# Parallel_CS_V3.net
KiCad netlist of a schematic drawn in EAGLE
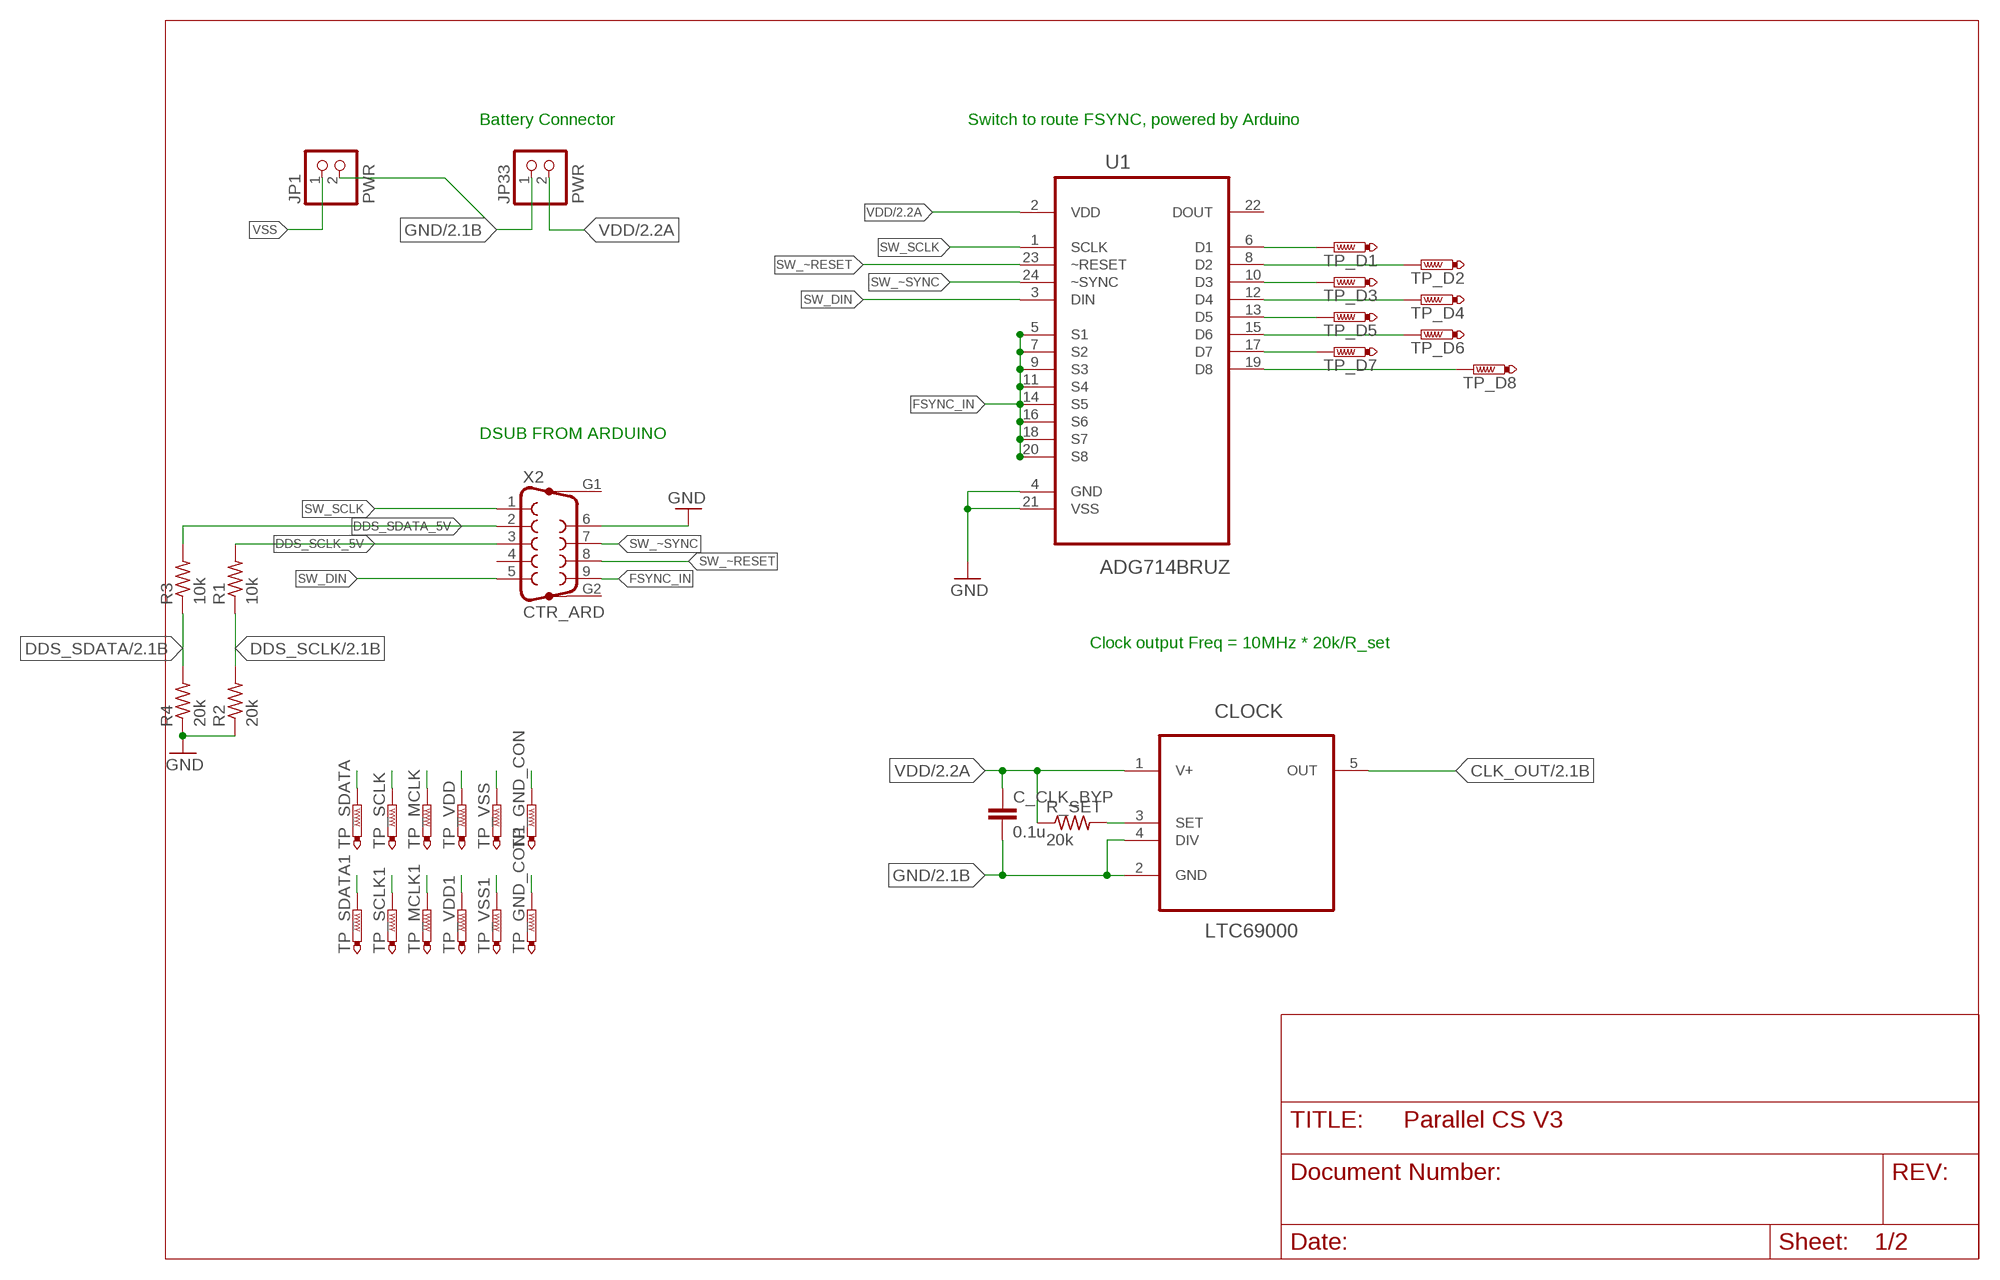
[diagram p0: schematic, sheet 1]
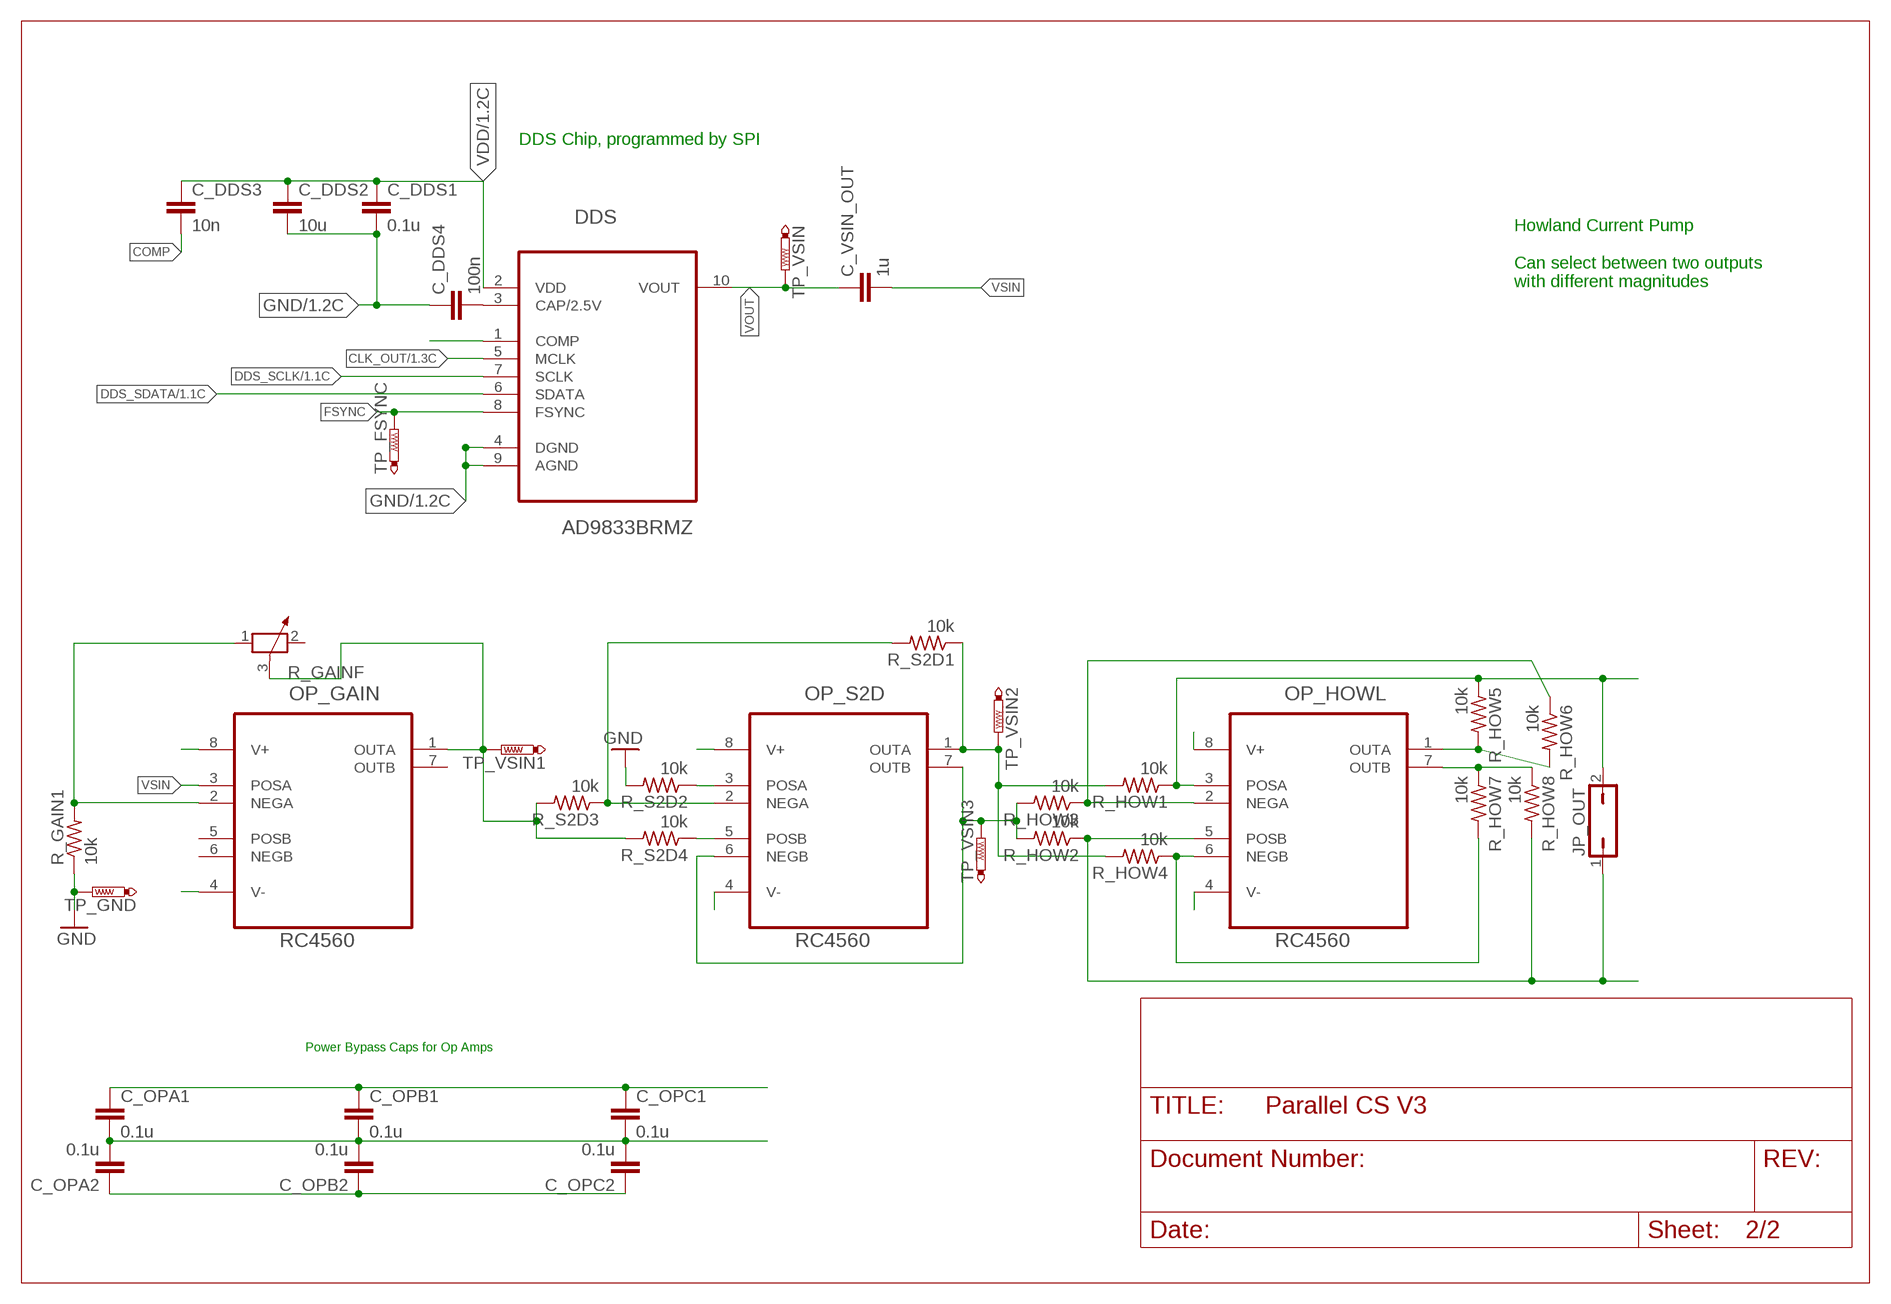
[diagram p1: schematic, sheet 2]

(export (version "E")
  (design (tool "Eeschema 10.0.6"))
  (components
    (comp (ref "C_DDS1")
      (value "0.1u")
      (footprint "eagle-import:C0805")
      (libsource (lib "eagle-import") (part "C-EUC0805"))
    )
    (comp (ref "C_DDS2")
      (value "10u")
      (footprint "eagle-import:C0805")
      (libsource (lib "eagle-import") (part "C-EUC0805"))
    )
    (comp (ref "C_DDS3")
      (value "10n")
      (footprint "eagle-import:C0805")
      (libsource (lib "eagle-import") (part "C-EUC0805"))
    )
    (comp (ref "C_DDS4")
      (value "100n")
      (footprint "eagle-import:C0805")
      (libsource (lib "eagle-import") (part "C-EUC0805"))
    )
    (comp (ref "C_OPA1")
      (value "0.1u")
      (footprint "eagle-import:C0805")
      (libsource (lib "eagle-import") (part "C-EUC0805"))
    )
    (comp (ref "C_OPA2")
      (value "0.1u")
      (footprint "eagle-import:C0805")
      (libsource (lib "eagle-import") (part "C-EUC0805"))
    )
    (comp (ref "C_OPB1")
      (value "0.1u")
      (footprint "eagle-import:C0805")
      (libsource (lib "eagle-import") (part "C-EUC0805"))
    )
    (comp (ref "C_OPB2")
      (value "0.1u")
      (footprint "eagle-import:C0805")
      (libsource (lib "eagle-import") (part "C-EUC0805"))
    )
    (comp (ref "C_OPC1")
      (value "0.1u")
      (footprint "eagle-import:C0805")
      (libsource (lib "eagle-import") (part "C-EUC0805"))
    )
    (comp (ref "C_OPC2")
      (value "0.1u")
      (footprint "eagle-import:C0805")
      (libsource (lib "eagle-import") (part "C-EUC0805"))
    )
    (comp (ref "C_VSIN_OUT")
      (value "1u")
      (footprint "eagle-import:C0805")
      (libsource (lib "eagle-import") (part "C-EUC0805"))
    )
    (comp (ref "DDS")
      (value "AD9833BRMZ")
      (footprint "eagle-import:SOP50P490X110-10N")
      (libsource (lib "eagle-import") (part "AD9833BRMZ"))
    )
    (comp (ref "JP_OUT")
      (value "JP1Q")
      (footprint "eagle-import:JP1")
      (libsource (lib "eagle-import") (part "JP1Q"))
    )
    (comp (ref "OP_GAIN")
      (value "RC4560")
      (footprint "eagle-import:DIL08")
      (libsource (lib "eagle-import") (part "RC4560"))
    )
    (comp (ref "OP_HOWL")
      (value "RC4560")
      (footprint "eagle-import:DIL08")
      (libsource (lib "eagle-import") (part "RC4560"))
    )
    (comp (ref "OP_S2D")
      (value "RC4560")
      (footprint "eagle-import:DIL08")
      (libsource (lib "eagle-import") (part "RC4560"))
    )
    (comp (ref "R_GAIN1")
      (value "10k")
      (footprint "eagle-import:R0805")
      (libsource (lib "eagle-import") (part "R-US_R0805"))
    )
    (comp (ref "R_GAINF")
      (value "POTENTIOMETER_PT-10")
      (footprint "eagle-import:PT-10")
      (libsource (lib "eagle-import") (part "POTENTIOMETER_PT-10"))
    )
    (comp (ref "R_HOW1")
      (value "10k")
      (footprint "eagle-import:R0805")
      (libsource (lib "eagle-import") (part "R-US_R0805"))
    )
    (comp (ref "R_HOW2")
      (value "10k")
      (footprint "eagle-import:R0805")
      (libsource (lib "eagle-import") (part "R-US_R0805"))
    )
    (comp (ref "R_HOW3")
      (value "10k")
      (footprint "eagle-import:R0805")
      (libsource (lib "eagle-import") (part "R-US_R0805"))
    )
    (comp (ref "R_HOW4")
      (value "10k")
      (footprint "eagle-import:R0805")
      (libsource (lib "eagle-import") (part "R-US_R0805"))
    )
    (comp (ref "R_HOW5")
      (value "10k")
      (footprint "eagle-import:R0805")
      (libsource (lib "eagle-import") (part "R-US_R0805"))
    )
    (comp (ref "R_HOW6")
      (value "10k")
      (footprint "eagle-import:R0805")
      (libsource (lib "eagle-import") (part "R-US_R0805"))
    )
    (comp (ref "R_HOW7")
      (value "10k")
      (footprint "eagle-import:R0805")
      (libsource (lib "eagle-import") (part "R-US_R0805"))
    )
    (comp (ref "R_HOW8")
      (value "10k")
      (footprint "eagle-import:R0805")
      (libsource (lib "eagle-import") (part "R-US_R0805"))
    )
    (comp (ref "R_S2D1")
      (value "10k")
      (footprint "eagle-import:R0805")
      (libsource (lib "eagle-import") (part "R-US_R0805"))
    )
    (comp (ref "R_S2D2")
      (value "10k")
      (footprint "eagle-import:R0805")
      (libsource (lib "eagle-import") (part "R-US_R0805"))
    )
    (comp (ref "R_S2D3")
      (value "10k")
      (footprint "eagle-import:R0805")
      (libsource (lib "eagle-import") (part "R-US_R0805"))
    )
    (comp (ref "R_S2D4")
      (value "10k")
      (footprint "eagle-import:R0805")
      (libsource (lib "eagle-import") (part "R-US_R0805"))
    )
    (comp (ref "TP_FSYNC")
      (value "PTR1PAD1-13")
      (footprint "eagle-import:P1-13")
      (libsource (lib "eagle-import") (part "PTR1PAD1-13"))
    )
    (comp (ref "TP_GND")
      (value "PTR1PAD1-13")
      (footprint "eagle-import:P1-13")
      (libsource (lib "eagle-import") (part "PTR1PAD1-13"))
    )
    (comp (ref "TP_VSIN")
      (value "PTR1PAD1-13")
      (footprint "eagle-import:P1-13")
      (libsource (lib "eagle-import") (part "PTR1PAD1-13"))
    )
    (comp (ref "TP_VSIN1")
      (value "PTR1PAD1-13")
      (footprint "eagle-import:P1-13")
      (libsource (lib "eagle-import") (part "PTR1PAD1-13"))
    )
    (comp (ref "TP_VSIN2")
      (value "PTR1PAD1-13")
      (footprint "eagle-import:P1-13")
      (libsource (lib "eagle-import") (part "PTR1PAD1-13"))
    )
    (comp (ref "TP_VSIN3")
      (value "PTR1PAD1-13")
      (footprint "eagle-import:P1-13")
      (libsource (lib "eagle-import") (part "PTR1PAD1-13"))
    )
    (comp (ref "CLOCK")
      (value "LTC69000")
      (footprint "eagle-import:SOT23-5L")
      (libsource (lib "eagle-import") (part "LTC69000"))
    )
    (comp (ref "C_CLK_BYP")
      (value "0.1u")
      (footprint "eagle-import:C0805")
      (libsource (lib "eagle-import") (part "C-EUC0805"))
    )
    (comp (ref "JP1")
      (value "PWR")
      (footprint "eagle-import:1X02")
      (libsource (lib "eagle-import") (part "PINHD-1X2"))
    )
    (comp (ref "JP33")
      (value "PWR")
      (footprint "eagle-import:1X02")
      (libsource (lib "eagle-import") (part "PINHD-1X2"))
    )
    (comp (ref "R1")
      (value "10k")
      (footprint "eagle-import:R0805")
      (libsource (lib "eagle-import") (part "resistor_R-US_R0805"))
    )
    (comp (ref "R2")
      (value "20k")
      (footprint "eagle-import:R0603")
      (libsource (lib "eagle-import") (part "resistor_R-US_R0603"))
    )
    (comp (ref "R3")
      (value "10k")
      (footprint "eagle-import:R0805")
      (libsource (lib "eagle-import") (part "resistor_R-US_R0805"))
    )
    (comp (ref "R4")
      (value "20k")
      (footprint "eagle-import:R0603")
      (libsource (lib "eagle-import") (part "resistor_R-US_R0603"))
    )
    (comp (ref "R_SET")
      (value "20k")
      (footprint "eagle-import:R0603")
      (libsource (lib "eagle-import") (part "resistor_R-US_R0603"))
    )
    (comp (ref "TP_D1")
      (value "PTR1PAD1-13")
      (footprint "eagle-import:P1-13")
      (libsource (lib "eagle-import") (part "PTR1PAD1-13"))
    )
    (comp (ref "TP_D2")
      (value "PTR1PAD1-13")
      (footprint "eagle-import:P1-13")
      (libsource (lib "eagle-import") (part "PTR1PAD1-13"))
    )
    (comp (ref "TP_D3")
      (value "PTR1PAD1-13")
      (footprint "eagle-import:P1-13")
      (libsource (lib "eagle-import") (part "PTR1PAD1-13"))
    )
    (comp (ref "TP_D4")
      (value "PTR1PAD1-13")
      (footprint "eagle-import:P1-13")
      (libsource (lib "eagle-import") (part "PTR1PAD1-13"))
    )
    (comp (ref "TP_D5")
      (value "PTR1PAD1-13")
      (footprint "eagle-import:P1-13")
      (libsource (lib "eagle-import") (part "PTR1PAD1-13"))
    )
    (comp (ref "TP_D6")
      (value "PTR1PAD1-13")
      (footprint "eagle-import:P1-13")
      (libsource (lib "eagle-import") (part "PTR1PAD1-13"))
    )
    (comp (ref "TP_D7")
      (value "PTR1PAD1-13")
      (footprint "eagle-import:P1-13")
      (libsource (lib "eagle-import") (part "PTR1PAD1-13"))
    )
    (comp (ref "TP_D8")
      (value "PTR1PAD1-13")
      (footprint "eagle-import:P1-13")
      (libsource (lib "eagle-import") (part "PTR1PAD1-13"))
    )
    (comp (ref "TP_GND_CON")
      (value "PTR1PAD1-13")
      (footprint "eagle-import:P1-13")
      (libsource (lib "eagle-import") (part "PTR1PAD1-13"))
    )
    (comp (ref "TP_GND_CON1")
      (value "PTR1PAD1-13")
      (footprint "eagle-import:P1-13")
      (libsource (lib "eagle-import") (part "PTR1PAD1-13"))
    )
    (comp (ref "TP_MCLK")
      (value "PTR1PAD1-13")
      (footprint "eagle-import:P1-13")
      (libsource (lib "eagle-import") (part "PTR1PAD1-13"))
    )
    (comp (ref "TP_MCLK1")
      (value "PTR1PAD1-13")
      (footprint "eagle-import:P1-13")
      (libsource (lib "eagle-import") (part "PTR1PAD1-13"))
    )
    (comp (ref "TP_SCLK")
      (value "PTR1PAD1-13")
      (footprint "eagle-import:P1-13")
      (libsource (lib "eagle-import") (part "PTR1PAD1-13"))
    )
    (comp (ref "TP_SCLK1")
      (value "PTR1PAD1-13")
      (footprint "eagle-import:P1-13")
      (libsource (lib "eagle-import") (part "PTR1PAD1-13"))
    )
    (comp (ref "TP_SDATA")
      (value "PTR1PAD1-13")
      (footprint "eagle-import:P1-13")
      (libsource (lib "eagle-import") (part "PTR1PAD1-13"))
    )
    (comp (ref "TP_SDATA1")
      (value "PTR1PAD1-13")
      (footprint "eagle-import:P1-13")
      (libsource (lib "eagle-import") (part "PTR1PAD1-13"))
    )
    (comp (ref "TP_VDD")
      (value "PTR1PAD1-13")
      (footprint "eagle-import:P1-13")
      (libsource (lib "eagle-import") (part "PTR1PAD1-13"))
    )
    (comp (ref "TP_VDD1")
      (value "PTR1PAD1-13")
      (footprint "eagle-import:P1-13")
      (libsource (lib "eagle-import") (part "PTR1PAD1-13"))
    )
    (comp (ref "TP_VSS")
      (value "PTR1PAD1-13")
      (footprint "eagle-import:P1-13")
      (libsource (lib "eagle-import") (part "PTR1PAD1-13"))
    )
    (comp (ref "TP_VSS1")
      (value "PTR1PAD1-13")
      (footprint "eagle-import:P1-13")
      (libsource (lib "eagle-import") (part "PTR1PAD1-13"))
    )
    (comp (ref "U1")
      (value "ADG714BRUZ")
      (footprint "eagle-import:SOP65P640X120-24N")
      (libsource (lib "eagle-import") (part "ADG714BRUZ"))
    )
    (comp (ref "X2")
      (value "CTR_ARD")
      (footprint "eagle-import:F09HP")
      (libsource (lib "eagle-import") (part "F09HP"))
    )
  )
  (nets
    (net (code "1") (name "CLK_OUT") (class "Default")
      (node (ref "CLOCK") (pin "5") (pinfunction "OUT_5") (pintype "output"))
      (node (ref "DDS") (pin "5") (pinfunction "MCLK_5") (pintype "input"))
      (node (ref "TP_MCLK") (pin "TP") (pinfunction "TP_TP") (pintype "input"))
      (node (ref "TP_MCLK1") (pin "TP") (pinfunction "TP_TP") (pintype "input"))
    )
    (net (code "2") (name "COMP") (class "Default")
      (node (ref "C_DDS3") (pin "2") (pinfunction "2_2") (pintype "passive"))
      (node (ref "DDS") (pin "1") (pinfunction "COMP_1") (pintype "passive"))
    )
    (net (code "3") (name "DDS_SCLK") (class "Default")
      (node (ref "DDS") (pin "7") (pinfunction "SCLK_7") (pintype "input"))
      (node (ref "R1") (pin "1") (pinfunction "1_1") (pintype "passive"))
      (node (ref "R2") (pin "2") (pinfunction "2_2") (pintype "passive"))
      (node (ref "TP_SCLK") (pin "TP") (pinfunction "TP_TP") (pintype "input"))
      (node (ref "TP_SCLK1") (pin "TP") (pinfunction "TP_TP") (pintype "input"))
    )
    (net (code "4") (name "DDS_SCLK_5V") (class "Default")
      (node (ref "R1") (pin "2") (pinfunction "2_2") (pintype "passive"))
      (node (ref "X2") (pin "3") (pinfunction "3_3") (pintype "passive"))
    )
    (net (code "5") (name "DDS_SDATA") (class "Default")
      (node (ref "DDS") (pin "6") (pinfunction "SDATA_6") (pintype "input"))
      (node (ref "R3") (pin "1") (pinfunction "1_1") (pintype "passive"))
      (node (ref "R4") (pin "2") (pinfunction "2_2") (pintype "passive"))
      (node (ref "TP_SDATA") (pin "TP") (pinfunction "TP_TP") (pintype "input"))
      (node (ref "TP_SDATA1") (pin "TP") (pinfunction "TP_TP") (pintype "input"))
    )
    (net (code "6") (name "DDS_SDATA_5V") (class "Default")
      (node (ref "R3") (pin "2") (pinfunction "2_2") (pintype "passive"))
      (node (ref "X2") (pin "2") (pinfunction "2_2") (pintype "passive"))
    )
    (net (code "7") (name "FSYNC") (class "Default")
      (node (ref "DDS") (pin "8") (pinfunction "FSYNC_8") (pintype "input"))
      (node (ref "TP_FSYNC") (pin "TP") (pinfunction "TP_TP") (pintype "input"))
    )
    (net (code "8") (name "FSYNC_IN") (class "Default")
      (node (ref "U1") (pin "11") (pinfunction "S4_11") (pintype "bidirectional"))
      (node (ref "U1") (pin "14") (pinfunction "S5_14") (pintype "bidirectional"))
      (node (ref "U1") (pin "16") (pinfunction "S6_16") (pintype "bidirectional"))
      (node (ref "U1") (pin "18") (pinfunction "S7_18") (pintype "bidirectional"))
      (node (ref "U1") (pin "20") (pinfunction "S8_20") (pintype "bidirectional"))
      (node (ref "U1") (pin "5") (pinfunction "S1_5") (pintype "bidirectional"))
      (node (ref "U1") (pin "7") (pinfunction "S2_7") (pintype "bidirectional"))
      (node (ref "U1") (pin "9") (pinfunction "S3_9") (pintype "bidirectional"))
      (node (ref "X2") (pin "9") (pinfunction "9_9") (pintype "passive"))
    )
    (net (code "9") (name "GND") (class "Default")
      (node (ref "CLOCK") (pin "2") (pinfunction "GND_2") (pintype "passive"))
      (node (ref "CLOCK") (pin "4") (pinfunction "DIV_4") (pintype "input"))
      (node (ref "C_CLK_BYP") (pin "2") (pinfunction "2_2") (pintype "passive"))
      (node (ref "C_DDS1") (pin "2") (pinfunction "2_2") (pintype "passive"))
      (node (ref "C_DDS2") (pin "2") (pinfunction "2_2") (pintype "passive"))
      (node (ref "C_DDS4") (pin "1") (pinfunction "1_1") (pintype "passive"))
      (node (ref "C_OPA1") (pin "2") (pinfunction "2_2") (pintype "passive"))
      (node (ref "C_OPA2") (pin "2") (pinfunction "2_2") (pintype "passive"))
      (node (ref "C_OPB1") (pin "2") (pinfunction "2_2") (pintype "passive"))
      (node (ref "C_OPB2") (pin "2") (pinfunction "2_2") (pintype "passive"))
      (node (ref "C_OPC1") (pin "2") (pinfunction "2_2") (pintype "passive"))
      (node (ref "C_OPC2") (pin "2") (pinfunction "2_2") (pintype "passive"))
      (node (ref "DDS") (pin "4") (pinfunction "DGND_4") (pintype "passive"))
      (node (ref "DDS") (pin "9") (pinfunction "AGND_9") (pintype "passive"))
      (node (ref "JP1") (pin "2") (pinfunction "2_2") (pintype "passive"))
      (node (ref "JP33") (pin "1") (pinfunction "1_1") (pintype "passive"))
      (node (ref "R2") (pin "1") (pinfunction "1_1") (pintype "passive"))
      (node (ref "R4") (pin "1") (pinfunction "1_1") (pintype "passive"))
      (node (ref "R_GAIN1") (pin "1") (pinfunction "1_1") (pintype "passive"))
      (node (ref "R_S2D2") (pin "2") (pinfunction "2_2") (pintype "passive"))
      (node (ref "TP_GND") (pin "TP") (pinfunction "TP_TP") (pintype "input"))
      (node (ref "TP_GND_CON") (pin "TP") (pinfunction "TP_TP") (pintype "input"))
      (node (ref "TP_GND_CON1") (pin "TP") (pinfunction "TP_TP") (pintype "input"))
      (node (ref "U1") (pin "21") (pinfunction "VSS_21") (pintype "power_in"))
      (node (ref "U1") (pin "4") (pinfunction "GND_4") (pintype "passive"))
      (node (ref "X2") (pin "6") (pinfunction "6_6") (pintype "passive"))
    )
    (net (code "10") (name "Net-(CLOCK-SET)") (class "Default")
      (node (ref "CLOCK") (pin "3") (pinfunction "SET_3") (pintype "input"))
      (node (ref "R_SET") (pin "2") (pinfunction "2_2") (pintype "passive"))
    )
    (net (code "11") (name "Net-(DDS-CAP{slash}2.5V)") (class "Default")
      (node (ref "C_DDS4") (pin "2") (pinfunction "2_2") (pintype "passive"))
      (node (ref "DDS") (pin "3") (pinfunction "CAP/2.5V_3") (pintype "passive"))
    )
    (net (code "12") (name "Net-(OP_GAIN-NEGA)") (class "Default")
      (node (ref "OP_GAIN") (pin "2") (pinfunction "NEGA_2") (pintype "input"))
      (node (ref "R_GAIN1") (pin "2") (pinfunction "2_2") (pintype "passive"))
      (node (ref "R_GAINF") (pin "1") (pinfunction "1_1") (pintype "passive"))
    )
    (net (code "13") (name "Net-(OP_GAIN-OUTA)") (class "Default")
      (node (ref "OP_GAIN") (pin "1") (pinfunction "OUTA_1") (pintype "output"))
      (node (ref "R_GAINF") (pin "3") (pinfunction "3_3") (pintype "passive"))
      (node (ref "R_S2D3") (pin "2") (pinfunction "2_2") (pintype "passive"))
      (node (ref "R_S2D4") (pin "2") (pinfunction "2_2") (pintype "passive"))
      (node (ref "TP_VSIN1") (pin "TP") (pinfunction "TP_TP") (pintype "input"))
    )
    (net (code "14") (name "Net-(OP_HOWL-NEGA)") (class "Default")
      (node (ref "OP_HOWL") (pin "2") (pinfunction "NEGA_2") (pintype "input"))
      (node (ref "R_HOW3") (pin "1") (pinfunction "1_1") (pintype "passive"))
      (node (ref "R_HOW6") (pin "1") (pinfunction "1_1") (pintype "passive"))
    )
    (net (code "15") (name "Net-(OP_HOWL-NEGB)") (class "Default")
      (node (ref "OP_HOWL") (pin "6") (pinfunction "NEGB_6") (pintype "input"))
      (node (ref "R_HOW4") (pin "1") (pinfunction "1_1") (pintype "passive"))
      (node (ref "R_HOW7") (pin "2") (pinfunction "2_2") (pintype "passive"))
    )
    (net (code "16") (name "Net-(OP_HOWL-OUTA)") (class "Default")
      (node (ref "OP_HOWL") (pin "1") (pinfunction "OUTA_1") (pintype "output"))
      (node (ref "R_HOW5") (pin "2") (pinfunction "2_2") (pintype "passive"))
      (node (ref "R_HOW6") (pin "2") (pinfunction "2_2") (pintype "passive"))
    )
    (net (code "17") (name "Net-(OP_HOWL-OUTB)") (class "Default")
      (node (ref "OP_HOWL") (pin "7") (pinfunction "OUTB_7") (pintype "output"))
      (node (ref "R_HOW7") (pin "1") (pinfunction "1_1") (pintype "passive"))
      (node (ref "R_HOW8") (pin "1") (pinfunction "1_1") (pintype "passive"))
    )
    (net (code "18") (name "Net-(OP_HOWL-POSA)") (class "Default")
      (node (ref "JP_OUT") (pin "2") (pinfunction "2_2") (pintype "passive"))
      (node (ref "OP_HOWL") (pin "3") (pinfunction "POSA_3") (pintype "input"))
      (node (ref "R_HOW1") (pin "1") (pinfunction "1_1") (pintype "passive"))
      (node (ref "R_HOW5") (pin "1") (pinfunction "1_1") (pintype "passive"))
    )
    (net (code "19") (name "Net-(OP_HOWL-POSB)") (class "Default")
      (node (ref "JP_OUT") (pin "1") (pinfunction "1_1") (pintype "passive"))
      (node (ref "OP_HOWL") (pin "5") (pinfunction "POSB_5") (pintype "input"))
      (node (ref "R_HOW2") (pin "1") (pinfunction "1_1") (pintype "passive"))
      (node (ref "R_HOW8") (pin "2") (pinfunction "2_2") (pintype "passive"))
    )
    (net (code "20") (name "Net-(OP_S2D-NEGA)") (class "Default")
      (node (ref "OP_S2D") (pin "2") (pinfunction "NEGA_2") (pintype "input"))
      (node (ref "R_S2D1") (pin "2") (pinfunction "2_2") (pintype "passive"))
      (node (ref "R_S2D3") (pin "1") (pinfunction "1_1") (pintype "passive"))
    )
    (net (code "21") (name "Net-(OP_S2D-NEGB)") (class "Default")
      (node (ref "OP_S2D") (pin "6") (pinfunction "NEGB_6") (pintype "input"))
      (node (ref "OP_S2D") (pin "7") (pinfunction "OUTB_7") (pintype "output"))
      (node (ref "R_HOW2") (pin "2") (pinfunction "2_2") (pintype "passive"))
      (node (ref "R_HOW3") (pin "2") (pinfunction "2_2") (pintype "passive"))
      (node (ref "TP_VSIN3") (pin "TP") (pinfunction "TP_TP") (pintype "input"))
    )
    (net (code "22") (name "Net-(OP_S2D-OUTA)") (class "Default")
      (node (ref "OP_S2D") (pin "1") (pinfunction "OUTA_1") (pintype "output"))
      (node (ref "R_HOW1") (pin "2") (pinfunction "2_2") (pintype "passive"))
      (node (ref "R_HOW4") (pin "2") (pinfunction "2_2") (pintype "passive"))
      (node (ref "R_S2D1") (pin "1") (pinfunction "1_1") (pintype "passive"))
      (node (ref "TP_VSIN2") (pin "TP") (pinfunction "TP_TP") (pintype "input"))
    )
    (net (code "23") (name "Net-(OP_S2D-POSA)") (class "Default")
      (node (ref "OP_S2D") (pin "3") (pinfunction "POSA_3") (pintype "input"))
      (node (ref "R_S2D2") (pin "1") (pinfunction "1_1") (pintype "passive"))
    )
    (net (code "24") (name "Net-(OP_S2D-POSB)") (class "Default")
      (node (ref "OP_S2D") (pin "5") (pinfunction "POSB_5") (pintype "input"))
      (node (ref "R_S2D4") (pin "1") (pinfunction "1_1") (pintype "passive"))
    )
    (net (code "25") (name "Net-(U1-D1)") (class "Default")
      (node (ref "TP_D1") (pin "TP") (pinfunction "TP_TP") (pintype "input"))
      (node (ref "U1") (pin "6") (pinfunction "D1_6") (pintype "bidirectional"))
    )
    (net (code "26") (name "Net-(U1-D2)") (class "Default")
      (node (ref "TP_D2") (pin "TP") (pinfunction "TP_TP") (pintype "input"))
      (node (ref "U1") (pin "8") (pinfunction "D2_8") (pintype "bidirectional"))
    )
    (net (code "27") (name "Net-(U1-D3)") (class "Default")
      (node (ref "TP_D3") (pin "TP") (pinfunction "TP_TP") (pintype "input"))
      (node (ref "U1") (pin "10") (pinfunction "D3_10") (pintype "bidirectional"))
    )
    (net (code "28") (name "Net-(U1-D4)") (class "Default")
      (node (ref "TP_D4") (pin "TP") (pinfunction "TP_TP") (pintype "input"))
      (node (ref "U1") (pin "12") (pinfunction "D4_12") (pintype "bidirectional"))
    )
    (net (code "29") (name "Net-(U1-D5)") (class "Default")
      (node (ref "TP_D5") (pin "TP") (pinfunction "TP_TP") (pintype "input"))
      (node (ref "U1") (pin "13") (pinfunction "D5_13") (pintype "bidirectional"))
    )
    (net (code "30") (name "Net-(U1-D6)") (class "Default")
      (node (ref "TP_D6") (pin "TP") (pinfunction "TP_TP") (pintype "input"))
      (node (ref "U1") (pin "15") (pinfunction "D6_15") (pintype "bidirectional"))
    )
    (net (code "31") (name "Net-(U1-D7)") (class "Default")
      (node (ref "TP_D7") (pin "TP") (pinfunction "TP_TP") (pintype "input"))
      (node (ref "U1") (pin "17") (pinfunction "D7_17") (pintype "bidirectional"))
    )
    (net (code "32") (name "Net-(U1-D8)") (class "Default")
      (node (ref "TP_D8") (pin "TP") (pinfunction "TP_TP") (pintype "input"))
      (node (ref "U1") (pin "19") (pinfunction "D8_19") (pintype "bidirectional"))
    )
    (net (code "33") (name "SW_DIN") (class "Default")
      (node (ref "U1") (pin "3") (pinfunction "DIN_3") (pintype "input"))
      (node (ref "X2") (pin "5") (pinfunction "5_5") (pintype "passive"))
    )
    (net (code "34") (name "SW_SCLK") (class "Default")
      (node (ref "U1") (pin "1") (pinfunction "SCLK_1") (pintype "input"))
      (node (ref "X2") (pin "1") (pinfunction "1_1") (pintype "passive"))
    )
    (net (code "35") (name "SW_~{RESET}") (class "Default")
      (node (ref "U1") (pin "23") (pinfunction "~{RESET}_23") (pintype "input"))
      (node (ref "X2") (pin "8") (pinfunction "8_8") (pintype "passive"))
    )
    (net (code "36") (name "SW_~{SYNC}") (class "Default")
      (node (ref "U1") (pin "24") (pinfunction "~{SYNC}_24") (pintype "input"))
      (node (ref "X2") (pin "7") (pinfunction "7_7") (pintype "passive"))
    )
    (net (code "37") (name "VDD") (class "Default")
      (node (ref "CLOCK") (pin "1") (pinfunction "V+_1") (pintype "power_in"))
      (node (ref "C_CLK_BYP") (pin "1") (pinfunction "1_1") (pintype "passive"))
      (node (ref "C_DDS1") (pin "1") (pinfunction "1_1") (pintype "passive"))
      (node (ref "C_DDS2") (pin "1") (pinfunction "1_1") (pintype "passive"))
      (node (ref "C_DDS3") (pin "1") (pinfunction "1_1") (pintype "passive"))
      (node (ref "C_OPA1") (pin "1") (pinfunction "1_1") (pintype "passive"))
      (node (ref "C_OPB1") (pin "1") (pinfunction "1_1") (pintype "passive"))
      (node (ref "C_OPC1") (pin "1") (pinfunction "1_1") (pintype "passive"))
      (node (ref "DDS") (pin "2") (pinfunction "VDD_2") (pintype "power_in"))
      (node (ref "JP33") (pin "2") (pinfunction "2_2") (pintype "passive"))
      (node (ref "OP_GAIN") (pin "8") (pinfunction "V+_8") (pintype "power_in"))
      (node (ref "OP_HOWL") (pin "8") (pinfunction "V+_8") (pintype "power_in"))
      (node (ref "OP_S2D") (pin "8") (pinfunction "V+_8") (pintype "power_in"))
      (node (ref "R_SET") (pin "1") (pinfunction "1_1") (pintype "passive"))
      (node (ref "TP_VDD") (pin "TP") (pinfunction "TP_TP") (pintype "input"))
      (node (ref "TP_VDD1") (pin "TP") (pinfunction "TP_TP") (pintype "input"))
      (node (ref "U1") (pin "2") (pinfunction "VDD_2") (pintype "power_in"))
    )
    (net (code "38") (name "VOUT") (class "Default")
      (node (ref "C_VSIN_OUT") (pin "1") (pinfunction "1_1") (pintype "passive"))
      (node (ref "DDS") (pin "10") (pinfunction "VOUT_10") (pintype "output"))
      (node (ref "TP_VSIN") (pin "TP") (pinfunction "TP_TP") (pintype "input"))
    )
    (net (code "39") (name "VSIN") (class "Default")
      (node (ref "C_VSIN_OUT") (pin "2") (pinfunction "2_2") (pintype "passive"))
      (node (ref "OP_GAIN") (pin "3") (pinfunction "POSA_3") (pintype "input"))
    )
    (net (code "40") (name "VSS") (class "Default")
      (node (ref "C_OPA2") (pin "1") (pinfunction "1_1") (pintype "passive"))
      (node (ref "C_OPB2") (pin "1") (pinfunction "1_1") (pintype "passive"))
      (node (ref "C_OPC2") (pin "1") (pinfunction "1_1") (pintype "passive"))
      (node (ref "JP1") (pin "1") (pinfunction "1_1") (pintype "passive"))
      (node (ref "OP_GAIN") (pin "4") (pinfunction "V-_4") (pintype "power_in"))
      (node (ref "OP_HOWL") (pin "4") (pinfunction "V-_4") (pintype "power_in"))
      (node (ref "OP_S2D") (pin "4") (pinfunction "V-_4") (pintype "power_in"))
      (node (ref "TP_VSS") (pin "TP") (pinfunction "TP_TP") (pintype "input"))
      (node (ref "TP_VSS1") (pin "TP") (pinfunction "TP_TP") (pintype "input"))
    )
    (net (code "41") (name "unconnected-(OP_GAIN-NEGB-Pad6)") (class "Default")
      (node (ref "OP_GAIN") (pin "6") (pinfunction "NEGB_6") (pintype "input"))
    )
    (net (code "42") (name "unconnected-(OP_GAIN-OUTB-Pad7)") (class "Default")
      (node (ref "OP_GAIN") (pin "7") (pinfunction "OUTB_7") (pintype "output"))
    )
    (net (code "43") (name "unconnected-(OP_GAIN-POSB-Pad5)") (class "Default")
      (node (ref "OP_GAIN") (pin "5") (pinfunction "POSB_5") (pintype "input"))
    )
    (net (code "44") (name "unconnected-(R_GAINF-Pad2)") (class "Default")
      (node (ref "R_GAINF") (pin "2") (pinfunction "2_2") (pintype "passive"))
    )
    (net (code "45") (name "unconnected-(U1-DOUT-Pad22)") (class "Default")
      (node (ref "U1") (pin "22") (pinfunction "DOUT_22") (pintype "output"))
    )
    (net (code "46") (name "unconnected-(X2-Pad4)") (class "Default")
      (node (ref "X2") (pin "4") (pinfunction "4_4") (pintype "passive"))
    )
    (net (code "47") (name "unconnected-(X2-PadG1)") (class "Default")
      (node (ref "X2") (pin "G1") (pinfunction "G1_G1") (pintype "passive"))
    )
    (net (code "48") (name "unconnected-(X2-PadG2)") (class "Default")
      (node (ref "X2") (pin "G2") (pinfunction "G2_G2") (pintype "passive"))
    )
  )
)
